# Smart_Grid_Schematic.net
KiCad netlist of a schematic drawn in Altium Designer
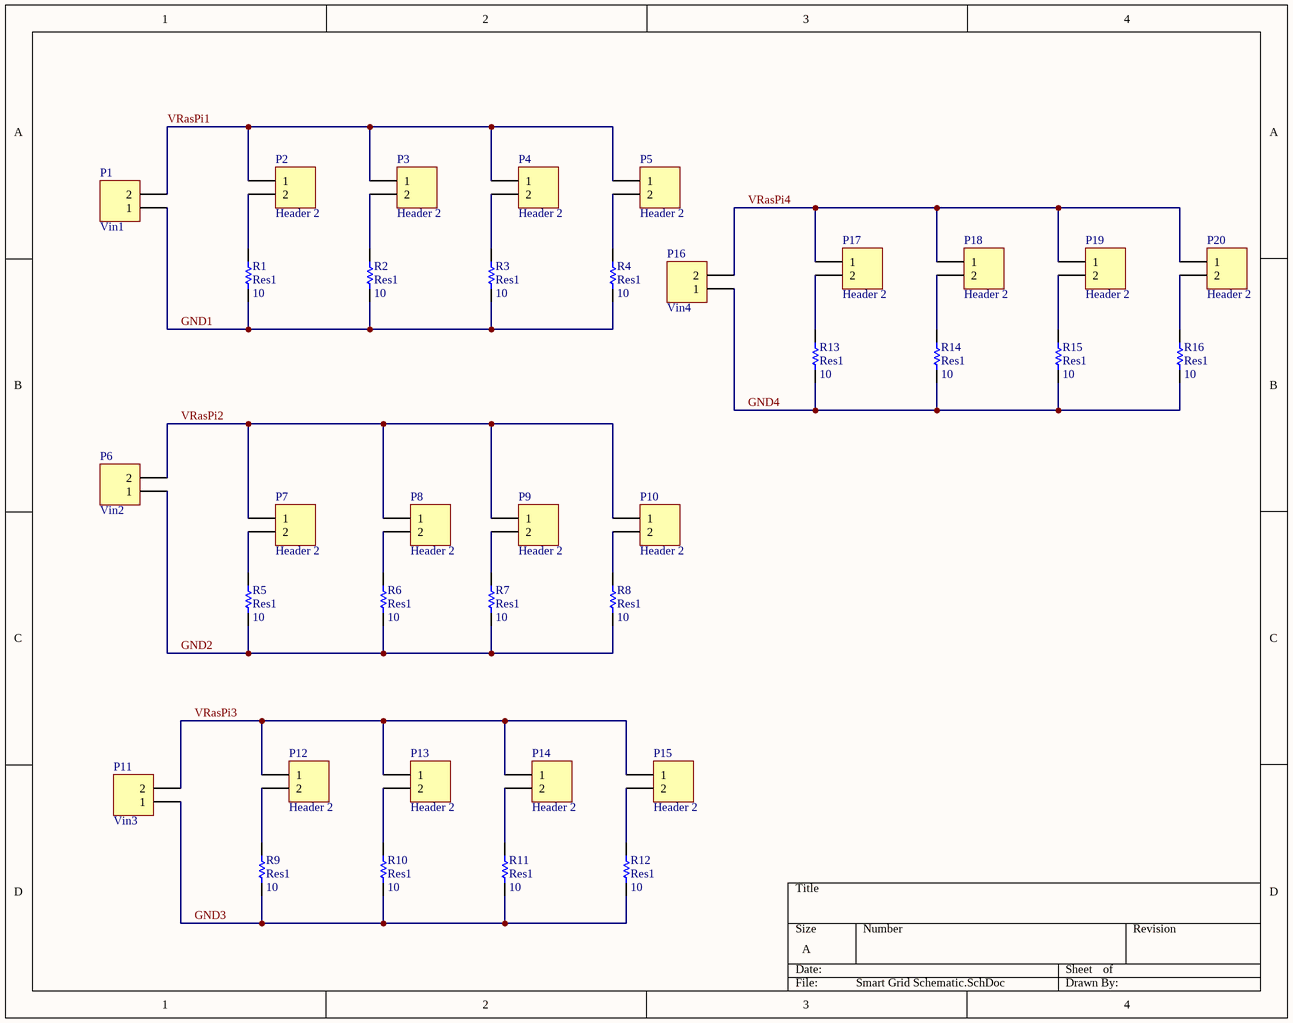
[diagram p0: Smart Grid Schematic.SchDoc]

(export (version "E")
  (design (tool "Eeschema 10.0.6"))
  (components
    (comp (ref "P1")
      (value "Vin1")
      (footprint "HDR1X2")
      (description "Header, 2-Pin")
      (fields (field (name "PUBLISHER") "Altium Limited"))
      (libsource (lib "Miscellaneous Connectors") (part "Header 2"))
    )
    (comp (ref "P2")
      (value "Header 2")
      (footprint "HDR1X2")
      (description "Header, 2-Pin")
      (fields (field (name "PUBLISHER") "Altium Limited"))
      (libsource (lib "") (part "Header 2_1"))
    )
    (comp (ref "P3")
      (value "Header 2")
      (footprint "HDR1X2")
      (description "Header, 2-Pin")
      (fields (field (name "PUBLISHER") "Altium Limited"))
      (libsource (lib "") (part "Header 2_1"))
    )
    (comp (ref "P4")
      (value "Header 2")
      (footprint "HDR1X2")
      (description "Header, 2-Pin")
      (fields (field (name "PUBLISHER") "Altium Limited"))
      (libsource (lib "") (part "Header 2_1"))
    )
    (comp (ref "P5")
      (value "Header 2")
      (footprint "HDR1X2")
      (description "Header, 2-Pin")
      (fields (field (name "PUBLISHER") "Altium Limited"))
      (libsource (lib "") (part "Header 2_1"))
    )
    (comp (ref "P6")
      (value "Vin2")
      (footprint "HDR1X2")
      (description "Header, 2-Pin")
      (fields (field (name "PUBLISHER") "Altium Limited"))
      (libsource (lib "Miscellaneous Connectors") (part "Header 2"))
    )
    (comp (ref "P7")
      (value "Header 2")
      (footprint "HDR1X2")
      (description "Header, 2-Pin")
      (fields (field (name "PUBLISHER") "Altium Limited"))
      (libsource (lib "") (part "Header 2_1"))
    )
    (comp (ref "P8")
      (value "Header 2")
      (footprint "HDR1X2")
      (description "Header, 2-Pin")
      (fields (field (name "PUBLISHER") "Altium Limited"))
      (libsource (lib "") (part "Header 2_1"))
    )
    (comp (ref "P9")
      (value "Header 2")
      (footprint "HDR1X2")
      (description "Header, 2-Pin")
      (fields (field (name "PUBLISHER") "Altium Limited"))
      (libsource (lib "") (part "Header 2_1"))
    )
    (comp (ref "P10")
      (value "Header 2")
      (footprint "HDR1X2")
      (description "Header, 2-Pin")
      (fields (field (name "PUBLISHER") "Altium Limited"))
      (libsource (lib "") (part "Header 2_1"))
    )
    (comp (ref "P11")
      (value "Vin3")
      (footprint "HDR1X2")
      (description "Header, 2-Pin")
      (fields (field (name "PUBLISHER") "Altium Limited"))
      (libsource (lib "Miscellaneous Connectors") (part "Header 2"))
    )
    (comp (ref "P12")
      (value "Header 2")
      (footprint "HDR1X2")
      (description "Header, 2-Pin")
      (fields (field (name "PUBLISHER") "Altium Limited"))
      (libsource (lib "") (part "Header 2_1"))
    )
    (comp (ref "P13")
      (value "Header 2")
      (footprint "HDR1X2")
      (description "Header, 2-Pin")
      (fields (field (name "PUBLISHER") "Altium Limited"))
      (libsource (lib "") (part "Header 2_1"))
    )
    (comp (ref "P14")
      (value "Header 2")
      (footprint "HDR1X2")
      (description "Header, 2-Pin")
      (fields (field (name "PUBLISHER") "Altium Limited"))
      (libsource (lib "") (part "Header 2_1"))
    )
    (comp (ref "P15")
      (value "Header 2")
      (footprint "HDR1X2")
      (description "Header, 2-Pin")
      (fields (field (name "PUBLISHER") "Altium Limited"))
      (libsource (lib "") (part "Header 2_1"))
    )
    (comp (ref "P16")
      (value "Vin4")
      (footprint "HDR1X2")
      (description "Header, 2-Pin")
      (fields (field (name "PUBLISHER") "Altium Limited"))
      (libsource (lib "Miscellaneous Connectors") (part "Header 2"))
    )
    (comp (ref "P17")
      (value "Header 2")
      (footprint "HDR1X2")
      (description "Header, 2-Pin")
      (fields (field (name "PUBLISHER") "Altium Limited"))
      (libsource (lib "") (part "Header 2_1"))
    )
    (comp (ref "P18")
      (value "Header 2")
      (footprint "HDR1X2")
      (description "Header, 2-Pin")
      (fields (field (name "PUBLISHER") "Altium Limited"))
      (libsource (lib "") (part "Header 2_1"))
    )
    (comp (ref "P19")
      (value "Header 2")
      (footprint "HDR1X2")
      (description "Header, 2-Pin")
      (fields (field (name "PUBLISHER") "Altium Limited"))
      (libsource (lib "") (part "Header 2_1"))
    )
    (comp (ref "P20")
      (value "Header 2")
      (footprint "HDR1X2")
      (description "Header, 2-Pin")
      (fields (field (name "PUBLISHER") "Altium Limited"))
      (libsource (lib "") (part "Header 2_1"))
    )
    (comp (ref "R1")
      (value "Res1")
      (footprint "AXIAL-0.3")
      (description "Resistor")
      (fields (field (name "ALTIUM_VALUE") "10") (field (name "PUBLISHER") "Altium Limited"))
      (libsource (lib "Miscellaneous Devices") (part "Res1"))
    )
    (comp (ref "R2")
      (value "Res1")
      (footprint "AXIAL-0.3")
      (description "Resistor")
      (fields (field (name "ALTIUM_VALUE") "10") (field (name "PUBLISHER") "Altium Limited"))
      (libsource (lib "Miscellaneous Devices") (part "Res1"))
    )
    (comp (ref "R3")
      (value "Res1")
      (footprint "AXIAL-0.3")
      (description "Resistor")
      (fields (field (name "ALTIUM_VALUE") "10") (field (name "PUBLISHER") "Altium Limited"))
      (libsource (lib "Miscellaneous Devices") (part "Res1"))
    )
    (comp (ref "R4")
      (value "Res1")
      (footprint "AXIAL-0.3")
      (description "Resistor")
      (fields (field (name "ALTIUM_VALUE") "10") (field (name "PUBLISHER") "Altium Limited"))
      (libsource (lib "Miscellaneous Devices") (part "Res1"))
    )
    (comp (ref "R5")
      (value "Res1")
      (footprint "AXIAL-0.3")
      (description "Resistor")
      (fields (field (name "ALTIUM_VALUE") "10") (field (name "PUBLISHER") "Altium Limited"))
      (libsource (lib "Miscellaneous Devices") (part "Res1"))
    )
    (comp (ref "R6")
      (value "Res1")
      (footprint "AXIAL-0.3")
      (description "Resistor")
      (fields (field (name "ALTIUM_VALUE") "10") (field (name "PUBLISHER") "Altium Limited"))
      (libsource (lib "Miscellaneous Devices") (part "Res1"))
    )
    (comp (ref "R7")
      (value "Res1")
      (footprint "AXIAL-0.3")
      (description "Resistor")
      (fields (field (name "ALTIUM_VALUE") "10") (field (name "PUBLISHER") "Altium Limited"))
      (libsource (lib "Miscellaneous Devices") (part "Res1"))
    )
    (comp (ref "R8")
      (value "Res1")
      (footprint "AXIAL-0.3")
      (description "Resistor")
      (fields (field (name "ALTIUM_VALUE") "10") (field (name "PUBLISHER") "Altium Limited"))
      (libsource (lib "Miscellaneous Devices") (part "Res1"))
    )
    (comp (ref "R9")
      (value "Res1")
      (footprint "AXIAL-0.3")
      (description "Resistor")
      (fields (field (name "ALTIUM_VALUE") "10") (field (name "PUBLISHER") "Altium Limited"))
      (libsource (lib "Miscellaneous Devices") (part "Res1"))
    )
    (comp (ref "R10")
      (value "Res1")
      (footprint "AXIAL-0.3")
      (description "Resistor")
      (fields (field (name "ALTIUM_VALUE") "10") (field (name "PUBLISHER") "Altium Limited"))
      (libsource (lib "Miscellaneous Devices") (part "Res1"))
    )
    (comp (ref "R11")
      (value "Res1")
      (footprint "AXIAL-0.3")
      (description "Resistor")
      (fields (field (name "ALTIUM_VALUE") "10") (field (name "PUBLISHER") "Altium Limited"))
      (libsource (lib "Miscellaneous Devices") (part "Res1"))
    )
    (comp (ref "R12")
      (value "Res1")
      (footprint "AXIAL-0.3")
      (description "Resistor")
      (fields (field (name "ALTIUM_VALUE") "10") (field (name "PUBLISHER") "Altium Limited"))
      (libsource (lib "Miscellaneous Devices") (part "Res1"))
    )
    (comp (ref "R13")
      (value "Res1")
      (footprint "AXIAL-0.3")
      (description "Resistor")
      (fields (field (name "ALTIUM_VALUE") "10") (field (name "PUBLISHER") "Altium Limited"))
      (libsource (lib "Miscellaneous Devices") (part "Res1"))
    )
    (comp (ref "R14")
      (value "Res1")
      (footprint "AXIAL-0.3")
      (description "Resistor")
      (fields (field (name "ALTIUM_VALUE") "10") (field (name "PUBLISHER") "Altium Limited"))
      (libsource (lib "Miscellaneous Devices") (part "Res1"))
    )
    (comp (ref "R15")
      (value "Res1")
      (footprint "AXIAL-0.3")
      (description "Resistor")
      (fields (field (name "ALTIUM_VALUE") "10") (field (name "PUBLISHER") "Altium Limited"))
      (libsource (lib "Miscellaneous Devices") (part "Res1"))
    )
    (comp (ref "R16")
      (value "Res1")
      (footprint "AXIAL-0.3")
      (description "Resistor")
      (fields (field (name "ALTIUM_VALUE") "10") (field (name "PUBLISHER") "Altium Limited"))
      (libsource (lib "Miscellaneous Devices") (part "Res1"))
    )
  )
  (nets
    (net (code "1") (name "/GND1") (class "Default")
      (node (ref "P1") (pin "1") (pinfunction "1_1") (pintype "passive"))
      (node (ref "R1") (pin "1") (pinfunction "1_1") (pintype "passive"))
      (node (ref "R2") (pin "1") (pinfunction "1_1") (pintype "passive"))
      (node (ref "R3") (pin "1") (pinfunction "1_1") (pintype "passive"))
      (node (ref "R4") (pin "1") (pinfunction "1_1") (pintype "passive"))
    )
    (net (code "2") (name "/GND2") (class "Default")
      (node (ref "P6") (pin "1") (pinfunction "1_1") (pintype "passive"))
      (node (ref "R5") (pin "1") (pinfunction "1_1") (pintype "passive"))
      (node (ref "R6") (pin "1") (pinfunction "1_1") (pintype "passive"))
      (node (ref "R7") (pin "1") (pinfunction "1_1") (pintype "passive"))
      (node (ref "R8") (pin "1") (pinfunction "1_1") (pintype "passive"))
    )
    (net (code "3") (name "/GND3") (class "Default")
      (node (ref "P11") (pin "1") (pinfunction "1_1") (pintype "passive"))
      (node (ref "R10") (pin "1") (pinfunction "1_1") (pintype "passive"))
      (node (ref "R11") (pin "1") (pinfunction "1_1") (pintype "passive"))
      (node (ref "R12") (pin "1") (pinfunction "1_1") (pintype "passive"))
      (node (ref "R9") (pin "1") (pinfunction "1_1") (pintype "passive"))
    )
    (net (code "4") (name "/GND4") (class "Default")
      (node (ref "P16") (pin "1") (pinfunction "1_1") (pintype "passive"))
      (node (ref "R13") (pin "1") (pinfunction "1_1") (pintype "passive"))
      (node (ref "R14") (pin "1") (pinfunction "1_1") (pintype "passive"))
      (node (ref "R15") (pin "1") (pinfunction "1_1") (pintype "passive"))
      (node (ref "R16") (pin "1") (pinfunction "1_1") (pintype "passive"))
    )
    (net (code "5") (name "/VRasPi1") (class "Default")
      (node (ref "P1") (pin "2") (pinfunction "2_2") (pintype "passive"))
      (node (ref "P2") (pin "1") (pinfunction "1_1") (pintype "passive"))
      (node (ref "P3") (pin "1") (pinfunction "1_1") (pintype "passive"))
      (node (ref "P4") (pin "1") (pinfunction "1_1") (pintype "passive"))
      (node (ref "P5") (pin "1") (pinfunction "1_1") (pintype "passive"))
    )
    (net (code "6") (name "/VRasPi2") (class "Default")
      (node (ref "P10") (pin "1") (pinfunction "1_1") (pintype "passive"))
      (node (ref "P6") (pin "2") (pinfunction "2_2") (pintype "passive"))
      (node (ref "P7") (pin "1") (pinfunction "1_1") (pintype "passive"))
      (node (ref "P8") (pin "1") (pinfunction "1_1") (pintype "passive"))
      (node (ref "P9") (pin "1") (pinfunction "1_1") (pintype "passive"))
    )
    (net (code "7") (name "/VRasPi3") (class "Default")
      (node (ref "P11") (pin "2") (pinfunction "2_2") (pintype "passive"))
      (node (ref "P12") (pin "1") (pinfunction "1_1") (pintype "passive"))
      (node (ref "P13") (pin "1") (pinfunction "1_1") (pintype "passive"))
      (node (ref "P14") (pin "1") (pinfunction "1_1") (pintype "passive"))
      (node (ref "P15") (pin "1") (pinfunction "1_1") (pintype "passive"))
    )
    (net (code "8") (name "/VRasPi4") (class "Default")
      (node (ref "P16") (pin "2") (pinfunction "2_2") (pintype "passive"))
      (node (ref "P17") (pin "1") (pinfunction "1_1") (pintype "passive"))
      (node (ref "P18") (pin "1") (pinfunction "1_1") (pintype "passive"))
      (node (ref "P19") (pin "1") (pinfunction "1_1") (pintype "passive"))
      (node (ref "P20") (pin "1") (pinfunction "1_1") (pintype "passive"))
    )
    (net (code "9") (name "Net-(P2-Pad2)") (class "Default")
      (node (ref "P2") (pin "2") (pinfunction "2_2") (pintype "passive"))
      (node (ref "R1") (pin "2") (pinfunction "2_2") (pintype "passive"))
    )
    (net (code "10") (name "Net-(P3-Pad2)") (class "Default")
      (node (ref "P3") (pin "2") (pinfunction "2_2") (pintype "passive"))
      (node (ref "R2") (pin "2") (pinfunction "2_2") (pintype "passive"))
    )
    (net (code "11") (name "Net-(P4-Pad2)") (class "Default")
      (node (ref "P4") (pin "2") (pinfunction "2_2") (pintype "passive"))
      (node (ref "R3") (pin "2") (pinfunction "2_2") (pintype "passive"))
    )
    (net (code "12") (name "Net-(P5-Pad2)") (class "Default")
      (node (ref "P5") (pin "2") (pinfunction "2_2") (pintype "passive"))
      (node (ref "R4") (pin "2") (pinfunction "2_2") (pintype "passive"))
    )
    (net (code "13") (name "Net-(P7-Pad2)") (class "Default")
      (node (ref "P7") (pin "2") (pinfunction "2_2") (pintype "passive"))
      (node (ref "R5") (pin "2") (pinfunction "2_2") (pintype "passive"))
    )
    (net (code "14") (name "Net-(P8-Pad2)") (class "Default")
      (node (ref "P8") (pin "2") (pinfunction "2_2") (pintype "passive"))
      (node (ref "R6") (pin "2") (pinfunction "2_2") (pintype "passive"))
    )
    (net (code "15") (name "Net-(P9-Pad2)") (class "Default")
      (node (ref "P9") (pin "2") (pinfunction "2_2") (pintype "passive"))
      (node (ref "R7") (pin "2") (pinfunction "2_2") (pintype "passive"))
    )
    (net (code "16") (name "Net-(P10-Pad2)") (class "Default")
      (node (ref "P10") (pin "2") (pinfunction "2_2") (pintype "passive"))
      (node (ref "R8") (pin "2") (pinfunction "2_2") (pintype "passive"))
    )
    (net (code "17") (name "Net-(P12-Pad2)") (class "Default")
      (node (ref "P12") (pin "2") (pinfunction "2_2") (pintype "passive"))
      (node (ref "R9") (pin "2") (pinfunction "2_2") (pintype "passive"))
    )
    (net (code "18") (name "Net-(P13-Pad2)") (class "Default")
      (node (ref "P13") (pin "2") (pinfunction "2_2") (pintype "passive"))
      (node (ref "R10") (pin "2") (pinfunction "2_2") (pintype "passive"))
    )
    (net (code "19") (name "Net-(P14-Pad2)") (class "Default")
      (node (ref "P14") (pin "2") (pinfunction "2_2") (pintype "passive"))
      (node (ref "R11") (pin "2") (pinfunction "2_2") (pintype "passive"))
    )
    (net (code "20") (name "Net-(P15-Pad2)") (class "Default")
      (node (ref "P15") (pin "2") (pinfunction "2_2") (pintype "passive"))
      (node (ref "R12") (pin "2") (pinfunction "2_2") (pintype "passive"))
    )
    (net (code "21") (name "Net-(P17-Pad2)") (class "Default")
      (node (ref "P17") (pin "2") (pinfunction "2_2") (pintype "passive"))
      (node (ref "R13") (pin "2") (pinfunction "2_2") (pintype "passive"))
    )
    (net (code "22") (name "Net-(P18-Pad2)") (class "Default")
      (node (ref "P18") (pin "2") (pinfunction "2_2") (pintype "passive"))
      (node (ref "R14") (pin "2") (pinfunction "2_2") (pintype "passive"))
    )
    (net (code "23") (name "Net-(P19-Pad2)") (class "Default")
      (node (ref "P19") (pin "2") (pinfunction "2_2") (pintype "passive"))
      (node (ref "R15") (pin "2") (pinfunction "2_2") (pintype "passive"))
    )
    (net (code "24") (name "Net-(P20-Pad2)") (class "Default")
      (node (ref "P20") (pin "2") (pinfunction "2_2") (pintype "passive"))
      (node (ref "R16") (pin "2") (pinfunction "2_2") (pintype "passive"))
    )
  )
)
